# EHDD_LAB_3.net
KiCad netlist of a schematic drawn in EAGLE
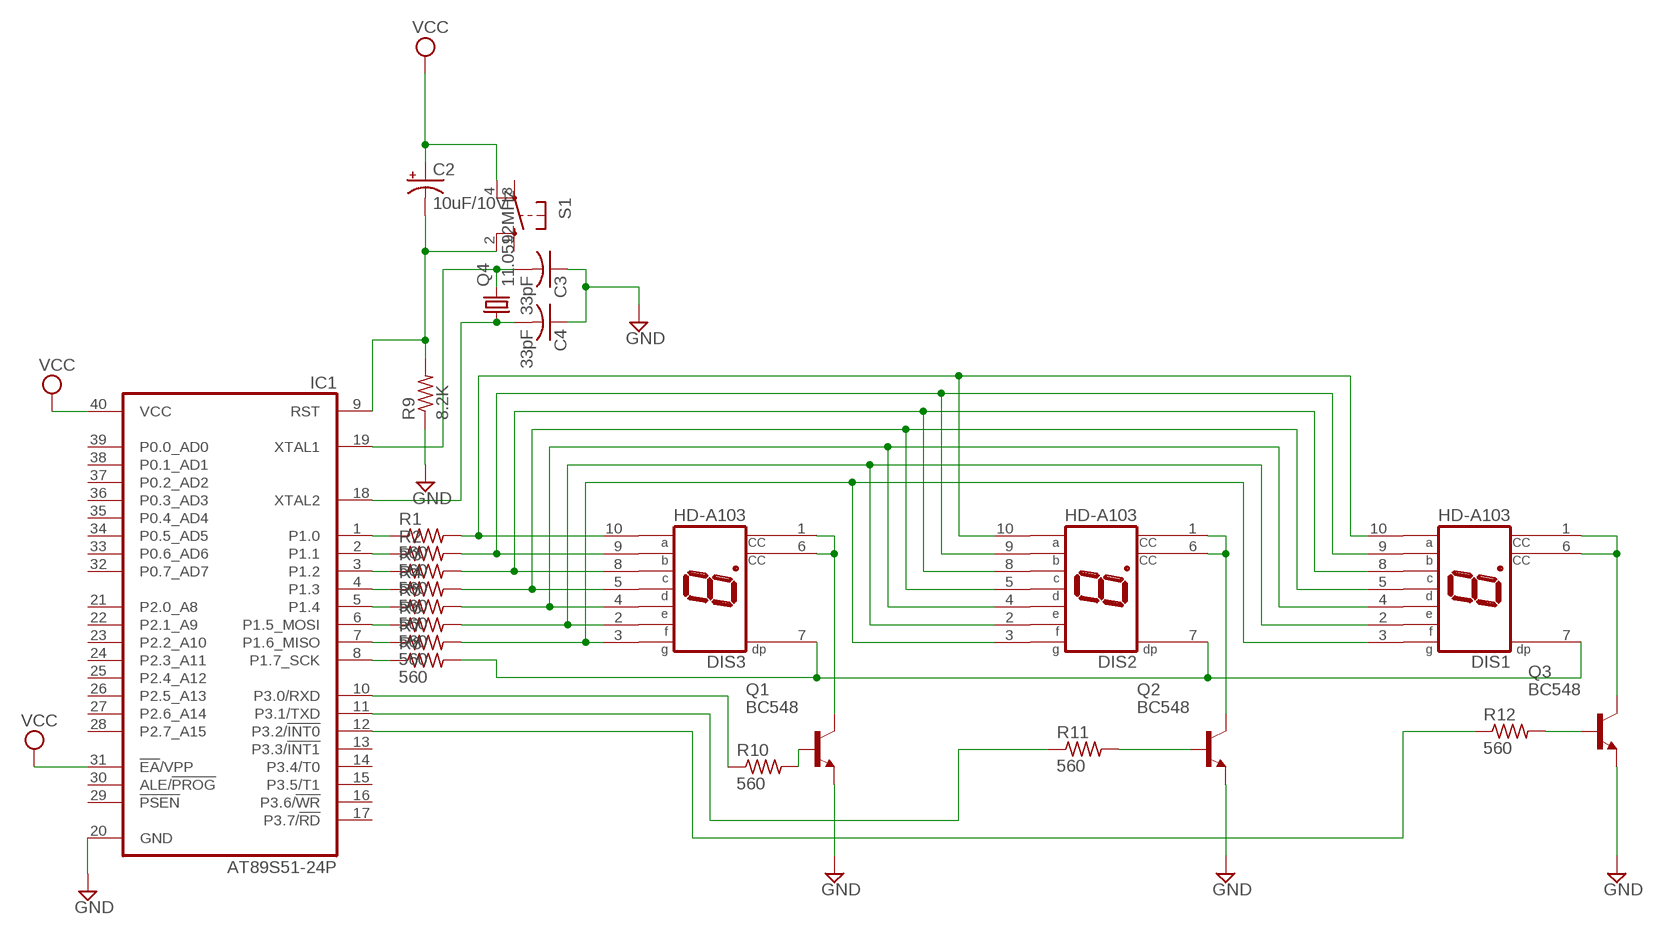
[diagram p0: schematic, sheet 1]

(export (version "E")
  (design (tool "Eeschema 10.0.6"))
  (components
    (comp (ref "C2")
      (value "10uF/10V")
      (footprint "eagle-import:E2-5")
      (libsource (lib "eagle-import") (part "CPOL-USE2-5"))
    )
    (comp (ref "C3")
      (value "33pF")
      (footprint "eagle-import:C025-050X050")
      (libsource (lib "eagle-import") (part "C-US025-050X050"))
    )
    (comp (ref "C4")
      (value "33pF")
      (footprint "eagle-import:C025-050X050")
      (libsource (lib "eagle-import") (part "C-US025-050X050"))
    )
    (comp (ref "DIS1")
      (value "HD-A103")
      (footprint "eagle-import:HDSP-A")
      (libsource (lib "eagle-import") (part "HD-A103"))
    )
    (comp (ref "DIS2")
      (value "HD-A103")
      (footprint "eagle-import:HDSP-A")
      (libsource (lib "eagle-import") (part "HD-A103"))
    )
    (comp (ref "DIS3")
      (value "HD-A103")
      (footprint "eagle-import:HDSP-A")
      (libsource (lib "eagle-import") (part "HD-A103"))
    )
    (comp (ref "IC1")
      (value "AT89S51-24P")
      (footprint "eagle-import:DIL40")
      (fields (field (name "MPN") "AT89S51-24PU"))
      (libsource (lib "eagle-import") (part "AT89S51-P24"))
    )
    (comp (ref "Q1")
      (value "BC548")
      (footprint "eagle-import:TO92-EBC")
      (libsource (lib "eagle-import") (part "BC548"))
    )
    (comp (ref "Q2")
      (value "BC548")
      (footprint "eagle-import:TO92-EBC")
      (libsource (lib "eagle-import") (part "BC548"))
    )
    (comp (ref "Q3")
      (value "BC548")
      (footprint "eagle-import:TO92-EBC")
      (libsource (lib "eagle-import") (part "BC548"))
    )
    (comp (ref "Q4")
      (value "11.0592MHz")
      (footprint "eagle-import:TC38H")
      (libsource (lib "eagle-import") (part "CRYSTALTC38H"))
    )
    (comp (ref "R1")
      (value "560")
      (footprint "eagle-import:0207_10")
      (libsource (lib "eagle-import") (part "R-US_0207/10"))
    )
    (comp (ref "R2")
      (value "560")
      (footprint "eagle-import:0207_10")
      (libsource (lib "eagle-import") (part "R-US_0207/10"))
    )
    (comp (ref "R3")
      (value "560")
      (footprint "eagle-import:0207_10")
      (libsource (lib "eagle-import") (part "R-US_0207/10"))
    )
    (comp (ref "R4")
      (value "560")
      (footprint "eagle-import:0207_10")
      (libsource (lib "eagle-import") (part "R-US_0207/10"))
    )
    (comp (ref "R5")
      (value "560")
      (footprint "eagle-import:0207_10")
      (libsource (lib "eagle-import") (part "R-US_0207/10"))
    )
    (comp (ref "R6")
      (value "560")
      (footprint "eagle-import:0207_10")
      (libsource (lib "eagle-import") (part "R-US_0207/10"))
    )
    (comp (ref "R7")
      (value "560")
      (footprint "eagle-import:0207_10")
      (libsource (lib "eagle-import") (part "R-US_0207/10"))
    )
    (comp (ref "R8")
      (value "560")
      (footprint "eagle-import:0207_10")
      (libsource (lib "eagle-import") (part "R-US_0207/10"))
    )
    (comp (ref "R9")
      (value "8.2K")
      (footprint "eagle-import:0207_10")
      (libsource (lib "eagle-import") (part "R-US_0207/10"))
    )
    (comp (ref "R10")
      (value "560")
      (footprint "eagle-import:0207_10")
      (libsource (lib "eagle-import") (part "R-US_0207/10"))
    )
    (comp (ref "R11")
      (value "560")
      (footprint "eagle-import:0207_10")
      (libsource (lib "eagle-import") (part "R-US_0207/10"))
    )
    (comp (ref "R12")
      (value "560")
      (footprint "eagle-import:0207_10")
      (libsource (lib "eagle-import") (part "R-US_0207/10"))
    )
    (comp (ref "S1")
      (value "10-XX")
      (footprint "eagle-import:B3F-10XX")
      (fields (field (name "MPN") "B3F-1000"))
      (libsource (lib "eagle-import") (part "10-XX"))
    )
  )
  (nets
    (net (code "1") (name "GND") (class "Default")
      (node (ref "C3") (pin "1") (pinfunction "1_1") (pintype "passive"))
      (node (ref "C4") (pin "1") (pinfunction "1_1") (pintype "passive"))
      (node (ref "IC1") (pin "20") (pinfunction "GND_20") (pintype "power_in"))
      (node (ref "Q1") (pin "E") (pinfunction "E_E") (pintype "passive"))
      (node (ref "Q2") (pin "E") (pinfunction "E_E") (pintype "passive"))
      (node (ref "Q3") (pin "E") (pinfunction "E_E") (pintype "passive"))
      (node (ref "R9") (pin "1") (pinfunction "1_1") (pintype "passive"))
    )
    (net (code "2") (name "Net-(DIS1-A)") (class "Default")
      (node (ref "DIS1") (pin "10") (pinfunction "A_10") (pintype "passive"))
      (node (ref "DIS2") (pin "10") (pinfunction "A_10") (pintype "passive"))
      (node (ref "DIS3") (pin "10") (pinfunction "A_10") (pintype "passive"))
      (node (ref "R1") (pin "2") (pinfunction "2_2") (pintype "passive"))
    )
    (net (code "3") (name "Net-(DIS1-B)") (class "Default")
      (node (ref "DIS1") (pin "9") (pinfunction "B_9") (pintype "passive"))
      (node (ref "DIS2") (pin "9") (pinfunction "B_9") (pintype "passive"))
      (node (ref "DIS3") (pin "9") (pinfunction "B_9") (pintype "passive"))
      (node (ref "R2") (pin "2") (pinfunction "2_2") (pintype "passive"))
    )
    (net (code "4") (name "Net-(DIS1-C)") (class "Default")
      (node (ref "DIS1") (pin "8") (pinfunction "C_8") (pintype "passive"))
      (node (ref "DIS2") (pin "8") (pinfunction "C_8") (pintype "passive"))
      (node (ref "DIS3") (pin "8") (pinfunction "C_8") (pintype "passive"))
      (node (ref "R3") (pin "2") (pinfunction "2_2") (pintype "passive"))
    )
    (net (code "5") (name "Net-(DIS1-CC-Pad1)") (class "Default")
      (node (ref "DIS1") (pin "1") (pinfunction "CC_1") (pintype "passive"))
      (node (ref "DIS1") (pin "6") (pinfunction "CC_6") (pintype "passive"))
      (node (ref "Q3") (pin "C") (pinfunction "C_C") (pintype "passive"))
    )
    (net (code "6") (name "Net-(DIS1-D)") (class "Default")
      (node (ref "DIS1") (pin "5") (pinfunction "D_5") (pintype "passive"))
      (node (ref "DIS2") (pin "5") (pinfunction "D_5") (pintype "passive"))
      (node (ref "DIS3") (pin "5") (pinfunction "D_5") (pintype "passive"))
      (node (ref "R4") (pin "2") (pinfunction "2_2") (pintype "passive"))
    )
    (net (code "7") (name "Net-(DIS1-DP)") (class "Default")
      (node (ref "DIS1") (pin "7") (pinfunction "DP_7") (pintype "passive"))
      (node (ref "DIS2") (pin "7") (pinfunction "DP_7") (pintype "passive"))
      (node (ref "DIS3") (pin "7") (pinfunction "DP_7") (pintype "passive"))
      (node (ref "R8") (pin "2") (pinfunction "2_2") (pintype "passive"))
    )
    (net (code "8") (name "Net-(DIS1-E)") (class "Default")
      (node (ref "DIS1") (pin "4") (pinfunction "E_4") (pintype "passive"))
      (node (ref "DIS2") (pin "4") (pinfunction "E_4") (pintype "passive"))
      (node (ref "DIS3") (pin "4") (pinfunction "E_4") (pintype "passive"))
      (node (ref "R5") (pin "2") (pinfunction "2_2") (pintype "passive"))
    )
    (net (code "9") (name "Net-(DIS1-F)") (class "Default")
      (node (ref "DIS1") (pin "2") (pinfunction "F_2") (pintype "passive"))
      (node (ref "DIS2") (pin "2") (pinfunction "F_2") (pintype "passive"))
      (node (ref "DIS3") (pin "2") (pinfunction "F_2") (pintype "passive"))
      (node (ref "R6") (pin "2") (pinfunction "2_2") (pintype "passive"))
    )
    (net (code "10") (name "Net-(DIS1-G)") (class "Default")
      (node (ref "DIS1") (pin "3") (pinfunction "G_3") (pintype "passive"))
      (node (ref "DIS2") (pin "3") (pinfunction "G_3") (pintype "passive"))
      (node (ref "DIS3") (pin "3") (pinfunction "G_3") (pintype "passive"))
      (node (ref "R7") (pin "2") (pinfunction "2_2") (pintype "passive"))
    )
    (net (code "11") (name "Net-(DIS2-CC-Pad1)") (class "Default")
      (node (ref "DIS2") (pin "1") (pinfunction "CC_1") (pintype "passive"))
      (node (ref "DIS2") (pin "6") (pinfunction "CC_6") (pintype "passive"))
      (node (ref "Q2") (pin "C") (pinfunction "C_C") (pintype "passive"))
    )
    (net (code "12") (name "Net-(DIS3-CC-Pad1)") (class "Default")
      (node (ref "DIS3") (pin "1") (pinfunction "CC_1") (pintype "passive"))
      (node (ref "DIS3") (pin "6") (pinfunction "CC_6") (pintype "passive"))
      (node (ref "Q1") (pin "C") (pinfunction "C_C") (pintype "passive"))
    )
    (net (code "13") (name "Net-(IC1-P1.0)") (class "Default")
      (node (ref "IC1") (pin "1") (pinfunction "P1.0_1") (pintype "bidirectional"))
      (node (ref "R1") (pin "1") (pinfunction "1_1") (pintype "passive"))
    )
    (net (code "14") (name "Net-(IC1-P1.1)") (class "Default")
      (node (ref "IC1") (pin "2") (pinfunction "P1.1_2") (pintype "bidirectional"))
      (node (ref "R2") (pin "1") (pinfunction "1_1") (pintype "passive"))
    )
    (net (code "15") (name "Net-(IC1-P1.2)") (class "Default")
      (node (ref "IC1") (pin "3") (pinfunction "P1.2_3") (pintype "bidirectional"))
      (node (ref "R3") (pin "1") (pinfunction "1_1") (pintype "passive"))
    )
    (net (code "16") (name "Net-(IC1-P1.3)") (class "Default")
      (node (ref "IC1") (pin "4") (pinfunction "P1.3_4") (pintype "bidirectional"))
      (node (ref "R4") (pin "1") (pinfunction "1_1") (pintype "passive"))
    )
    (net (code "17") (name "Net-(IC1-P1.4)") (class "Default")
      (node (ref "IC1") (pin "5") (pinfunction "P1.4_5") (pintype "bidirectional"))
      (node (ref "R5") (pin "1") (pinfunction "1_1") (pintype "passive"))
    )
    (net (code "18") (name "Net-(IC1-P1.5_MOSI)") (class "Default")
      (node (ref "IC1") (pin "6") (pinfunction "P1.5_MOSI_6") (pintype "bidirectional"))
      (node (ref "R6") (pin "1") (pinfunction "1_1") (pintype "passive"))
    )
    (net (code "19") (name "Net-(IC1-P1.6_MISO)") (class "Default")
      (node (ref "IC1") (pin "7") (pinfunction "P1.6_MISO_7") (pintype "bidirectional"))
      (node (ref "R7") (pin "1") (pinfunction "1_1") (pintype "passive"))
    )
    (net (code "20") (name "Net-(IC1-P1.7_SCK)") (class "Default")
      (node (ref "IC1") (pin "8") (pinfunction "P1.7_SCK_8") (pintype "bidirectional"))
      (node (ref "R8") (pin "1") (pinfunction "1_1") (pintype "passive"))
    )
    (net (code "21") (name "Net-(IC1-P3.0{slash}RXD)") (class "Default")
      (node (ref "IC1") (pin "10") (pinfunction "P3.0/RXD_10") (pintype "bidirectional"))
      (node (ref "R10") (pin "1") (pinfunction "1_1") (pintype "passive"))
    )
    (net (code "22") (name "Net-(IC1-P3.1{slash}TXD)") (class "Default")
      (node (ref "IC1") (pin "11") (pinfunction "P3.1/TXD_11") (pintype "bidirectional"))
      (node (ref "R11") (pin "1") (pinfunction "1_1") (pintype "passive"))
    )
    (net (code "23") (name "Net-(IC1-P3.2{slash}~{INT0})") (class "Default")
      (node (ref "IC1") (pin "12") (pinfunction "P3.2/~{INT0}_12") (pintype "bidirectional"))
      (node (ref "R12") (pin "1") (pinfunction "1_1") (pintype "passive"))
    )
    (net (code "24") (name "Net-(IC1-RST)") (class "Default")
      (node (ref "C2") (pin "-") (pinfunction "-_-") (pintype "passive"))
      (node (ref "IC1") (pin "9") (pinfunction "RST_9") (pintype "input"))
      (node (ref "R9") (pin "2") (pinfunction "2_2") (pintype "passive"))
      (node (ref "S1") (pin "2") (pinfunction "S1_2") (pintype "passive"))
    )
    (net (code "25") (name "Net-(IC1-XTAL1)") (class "Default")
      (node (ref "C3") (pin "2") (pinfunction "2_2") (pintype "passive"))
      (node (ref "IC1") (pin "19") (pinfunction "XTAL1_19") (pintype "input"))
      (node (ref "Q4") (pin "2") (pinfunction "2_2") (pintype "passive"))
    )
    (net (code "26") (name "Net-(IC1-XTAL2)") (class "Default")
      (node (ref "C4") (pin "2") (pinfunction "2_2") (pintype "passive"))
      (node (ref "IC1") (pin "18") (pinfunction "XTAL2_18") (pintype "input"))
      (node (ref "Q4") (pin "1") (pinfunction "1_1") (pintype "passive"))
    )
    (net (code "27") (name "Net-(Q1-PadB)") (class "Default")
      (node (ref "Q1") (pin "B") (pinfunction "B_B") (pintype "passive"))
      (node (ref "R10") (pin "2") (pinfunction "2_2") (pintype "passive"))
    )
    (net (code "28") (name "Net-(Q2-PadB)") (class "Default")
      (node (ref "Q2") (pin "B") (pinfunction "B_B") (pintype "passive"))
      (node (ref "R11") (pin "2") (pinfunction "2_2") (pintype "passive"))
    )
    (net (code "29") (name "Net-(Q3-PadB)") (class "Default")
      (node (ref "Q3") (pin "B") (pinfunction "B_B") (pintype "passive"))
      (node (ref "R12") (pin "2") (pinfunction "2_2") (pintype "passive"))
    )
    (net (code "30") (name "VCC") (class "Default")
      (node (ref "C2") (pin "+") (pinfunction "+_+") (pintype "passive"))
      (node (ref "IC1") (pin "31") (pinfunction "~{EA}/VPP_31") (pintype "input"))
      (node (ref "IC1") (pin "40") (pinfunction "VCC_40") (pintype "power_in"))
      (node (ref "S1") (pin "4") (pinfunction "P1_4") (pintype "passive"))
    )
    (net (code "31") (name "unconnected-(IC1-ALE{slash}~{PROG}-Pad30)") (class "Default")
      (node (ref "IC1") (pin "30") (pinfunction "ALE/~{PROG}_30") (pintype "output"))
    )
    (net (code "32") (name "unconnected-(IC1-P0.0_AD0-Pad39)") (class "Default")
      (node (ref "IC1") (pin "39") (pinfunction "P0.0_AD0_39") (pintype "bidirectional"))
    )
    (net (code "33") (name "unconnected-(IC1-P0.1_AD1-Pad38)") (class "Default")
      (node (ref "IC1") (pin "38") (pinfunction "P0.1_AD1_38") (pintype "bidirectional"))
    )
    (net (code "34") (name "unconnected-(IC1-P0.2_AD2-Pad37)") (class "Default")
      (node (ref "IC1") (pin "37") (pinfunction "P0.2_AD2_37") (pintype "bidirectional"))
    )
    (net (code "35") (name "unconnected-(IC1-P0.3_AD3-Pad36)") (class "Default")
      (node (ref "IC1") (pin "36") (pinfunction "P0.3_AD3_36") (pintype "bidirectional"))
    )
    (net (code "36") (name "unconnected-(IC1-P0.4_AD4-Pad35)") (class "Default")
      (node (ref "IC1") (pin "35") (pinfunction "P0.4_AD4_35") (pintype "bidirectional"))
    )
    (net (code "37") (name "unconnected-(IC1-P0.5_AD5-Pad34)") (class "Default")
      (node (ref "IC1") (pin "34") (pinfunction "P0.5_AD5_34") (pintype "bidirectional"))
    )
    (net (code "38") (name "unconnected-(IC1-P0.6_AD6-Pad33)") (class "Default")
      (node (ref "IC1") (pin "33") (pinfunction "P0.6_AD6_33") (pintype "bidirectional"))
    )
    (net (code "39") (name "unconnected-(IC1-P0.7_AD7-Pad32)") (class "Default")
      (node (ref "IC1") (pin "32") (pinfunction "P0.7_AD7_32") (pintype "bidirectional"))
    )
    (net (code "40") (name "unconnected-(IC1-P2.0_A8-Pad21)") (class "Default")
      (node (ref "IC1") (pin "21") (pinfunction "P2.0_A8_21") (pintype "bidirectional"))
    )
    (net (code "41") (name "unconnected-(IC1-P2.1_A9-Pad22)") (class "Default")
      (node (ref "IC1") (pin "22") (pinfunction "P2.1_A9_22") (pintype "bidirectional"))
    )
    (net (code "42") (name "unconnected-(IC1-P2.2_A10-Pad23)") (class "Default")
      (node (ref "IC1") (pin "23") (pinfunction "P2.2_A10_23") (pintype "bidirectional"))
    )
    (net (code "43") (name "unconnected-(IC1-P2.3_A11-Pad24)") (class "Default")
      (node (ref "IC1") (pin "24") (pinfunction "P2.3_A11_24") (pintype "bidirectional"))
    )
    (net (code "44") (name "unconnected-(IC1-P2.4_A12-Pad25)") (class "Default")
      (node (ref "IC1") (pin "25") (pinfunction "P2.4_A12_25") (pintype "bidirectional"))
    )
    (net (code "45") (name "unconnected-(IC1-P2.5_A13-Pad26)") (class "Default")
      (node (ref "IC1") (pin "26") (pinfunction "P2.5_A13_26") (pintype "bidirectional"))
    )
    (net (code "46") (name "unconnected-(IC1-P2.6_A14-Pad27)") (class "Default")
      (node (ref "IC1") (pin "27") (pinfunction "P2.6_A14_27") (pintype "bidirectional"))
    )
    (net (code "47") (name "unconnected-(IC1-P2.7_A15-Pad28)") (class "Default")
      (node (ref "IC1") (pin "28") (pinfunction "P2.7_A15_28") (pintype "bidirectional"))
    )
    (net (code "48") (name "unconnected-(IC1-P3.3{slash}~{INT1}-Pad13)") (class "Default")
      (node (ref "IC1") (pin "13") (pinfunction "P3.3/~{INT1}_13") (pintype "bidirectional"))
    )
    (net (code "49") (name "unconnected-(IC1-P3.4{slash}T0-Pad14)") (class "Default")
      (node (ref "IC1") (pin "14") (pinfunction "P3.4/T0_14") (pintype "bidirectional"))
    )
    (net (code "50") (name "unconnected-(IC1-P3.5{slash}T1-Pad15)") (class "Default")
      (node (ref "IC1") (pin "15") (pinfunction "P3.5/T1_15") (pintype "bidirectional"))
    )
    (net (code "51") (name "unconnected-(IC1-P3.6{slash}~{WR}-Pad16)") (class "Default")
      (node (ref "IC1") (pin "16") (pinfunction "P3.6/~{WR}_16") (pintype "bidirectional"))
    )
    (net (code "52") (name "unconnected-(IC1-P3.7{slash}~{RD}-Pad17)") (class "Default")
      (node (ref "IC1") (pin "17") (pinfunction "P3.7/~{RD}_17") (pintype "bidirectional"))
    )
    (net (code "53") (name "unconnected-(IC1-~{PSEN}-Pad29)") (class "Default")
      (node (ref "IC1") (pin "29") (pinfunction "~{PSEN}_29") (pintype "output"))
    )
    (net (code "54") (name "unconnected-(S1-P-Pad3)") (class "Default")
      (node (ref "S1") (pin "3") (pinfunction "P_3") (pintype "passive"))
    )
    (net (code "55") (name "unconnected-(S1-S-Pad1)") (class "Default")
      (node (ref "S1") (pin "1") (pinfunction "S_1") (pintype "passive"))
    )
  )
)
